# ra1.net
KiCad netlist of a schematic drawn in Altium Designer
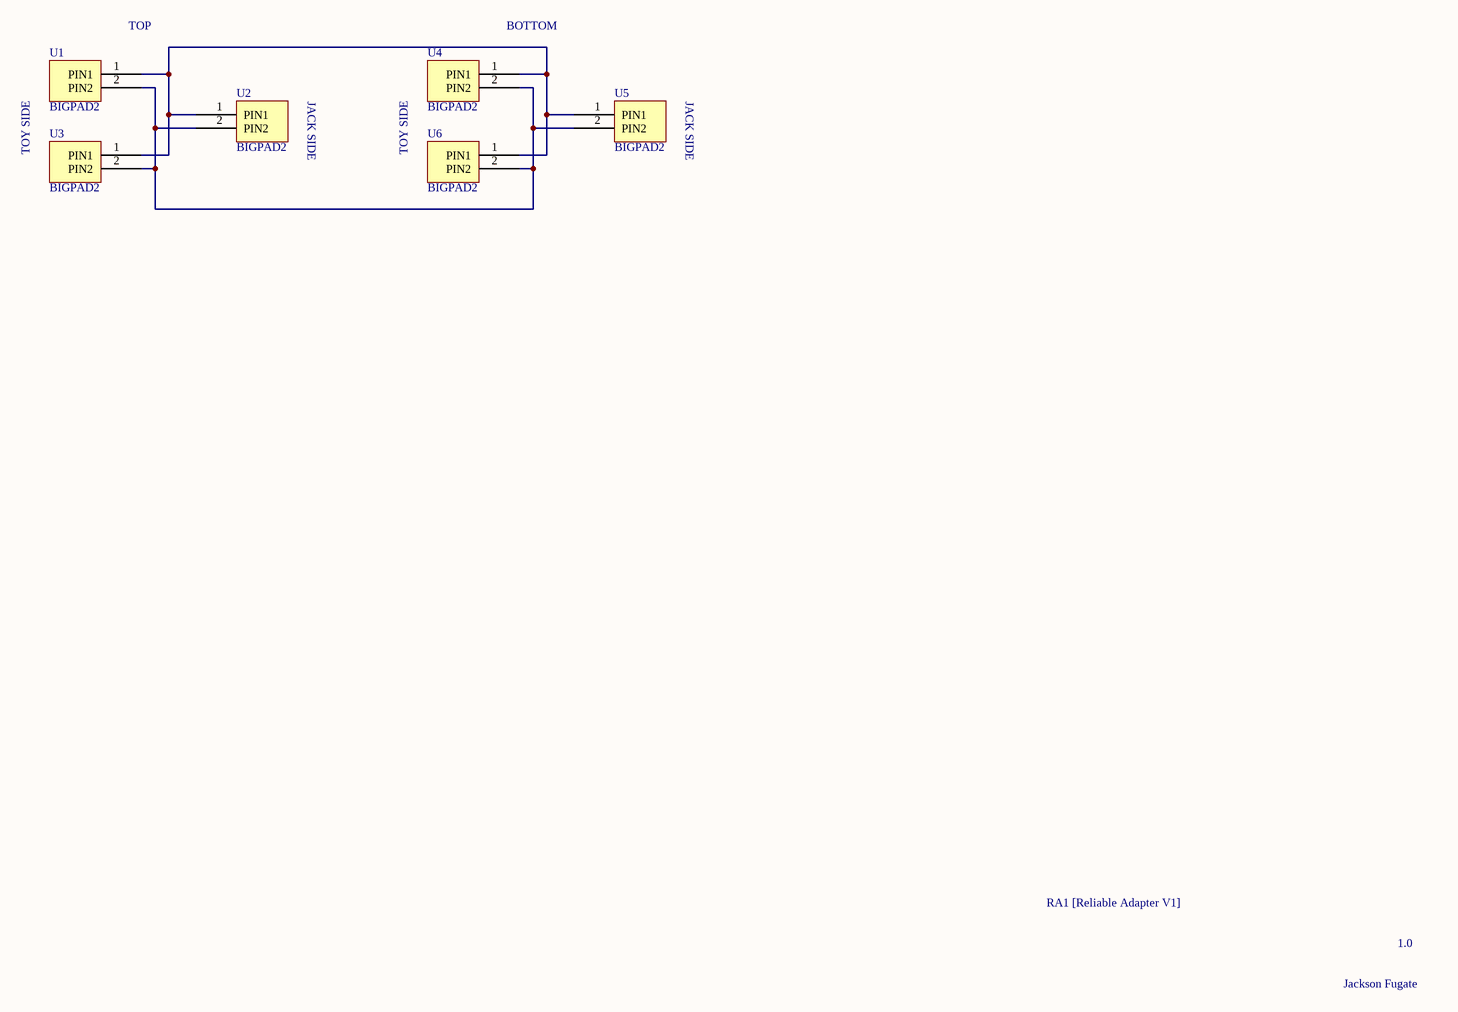
[diagram p0: ra1.SchDoc]

(export (version "E")
  (design (tool "Eeschema 10.0.6"))
  (components
    (comp (ref "U1")
      (value "BIGPAD2")
      (footprint "BIGPAD2")
      (libsource (lib "JF_master_lib") (part "BIGPAD2"))
    )
    (comp (ref "U2") (value "BIGPAD2") (footprint "BIGPAD2") (libsource (lib "") (part "BIGPAD2_1")))
    (comp (ref "U3")
      (value "BIGPAD2")
      (footprint "BIGPAD2")
      (libsource (lib "JF_master_lib") (part "BIGPAD2"))
    )
    (comp (ref "U4")
      (value "BIGPAD2")
      (footprint "BIGPAD2")
      (libsource (lib "JF_master_lib") (part "BIGPAD2"))
    )
    (comp (ref "U5") (value "BIGPAD2") (footprint "BIGPAD2") (libsource (lib "") (part "BIGPAD2_1")))
    (comp (ref "U6")
      (value "BIGPAD2")
      (footprint "BIGPAD2")
      (libsource (lib "JF_master_lib") (part "BIGPAD2"))
    )
  )
  (nets
    (net (code "1") (name "Net-(U1-PIN1)") (class "Default")
      (node (ref "U1") (pin "1") (pinfunction "PIN1_1") (pintype "passive"))
      (node (ref "U2") (pin "1") (pinfunction "PIN1_1") (pintype "passive"))
      (node (ref "U3") (pin "1") (pinfunction "PIN1_1") (pintype "passive"))
      (node (ref "U4") (pin "1") (pinfunction "PIN1_1") (pintype "passive"))
      (node (ref "U5") (pin "1") (pinfunction "PIN1_1") (pintype "passive"))
      (node (ref "U6") (pin "1") (pinfunction "PIN1_1") (pintype "passive"))
    )
    (net (code "2") (name "Net-(U1-PIN2)") (class "Default")
      (node (ref "U1") (pin "2") (pinfunction "PIN2_2") (pintype "passive"))
      (node (ref "U2") (pin "2") (pinfunction "PIN2_2") (pintype "passive"))
      (node (ref "U3") (pin "2") (pinfunction "PIN2_2") (pintype "passive"))
      (node (ref "U4") (pin "2") (pinfunction "PIN2_2") (pintype "passive"))
      (node (ref "U5") (pin "2") (pinfunction "PIN2_2") (pintype "passive"))
      (node (ref "U6") (pin "2") (pinfunction "PIN2_2") (pintype "passive"))
    )
  )
)
